# TC264MCU.net
KiCad netlist of a schematic drawn in Altium Designer
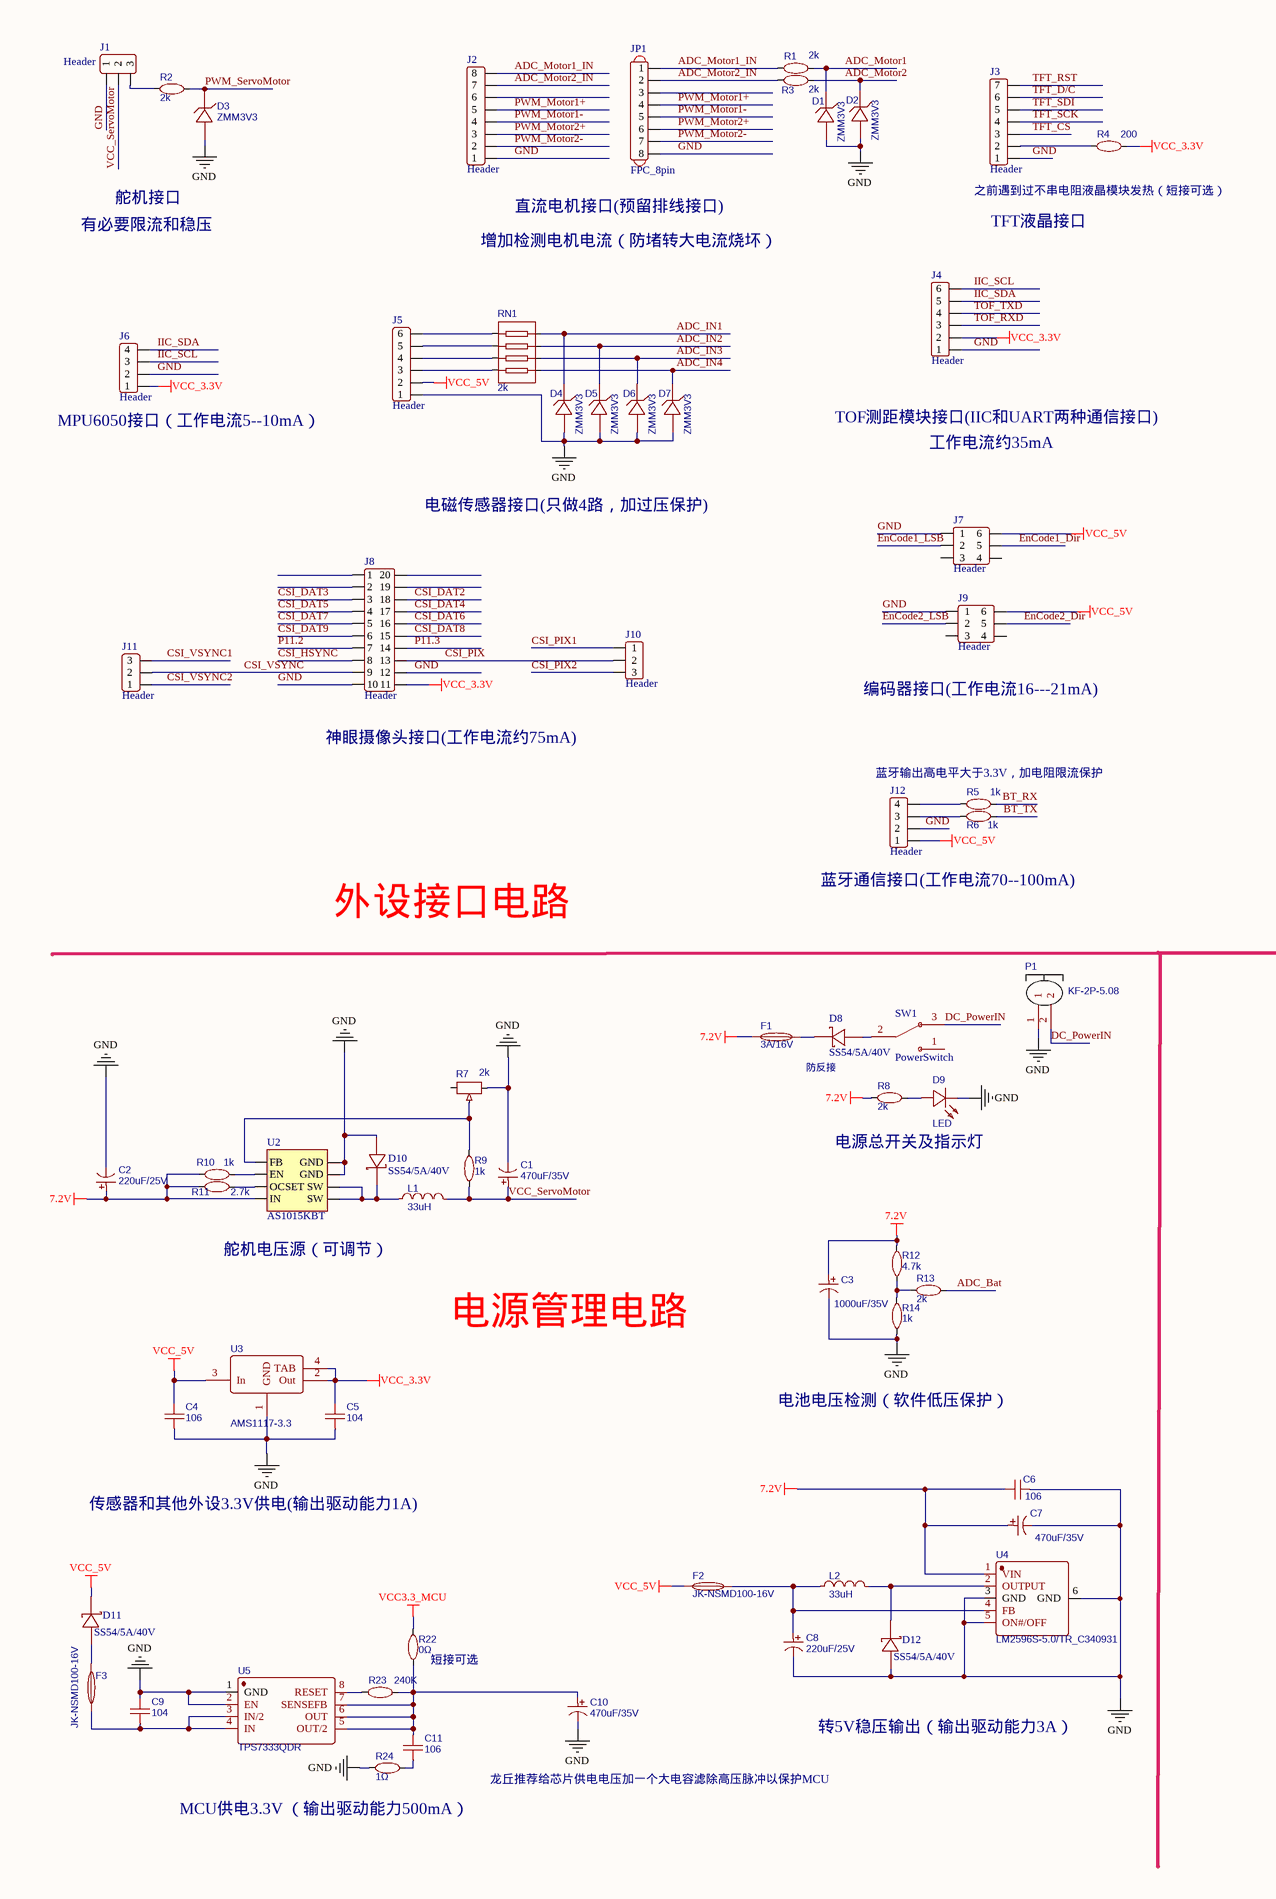
[diagram p0: TC264MCU.SchDoc, left]
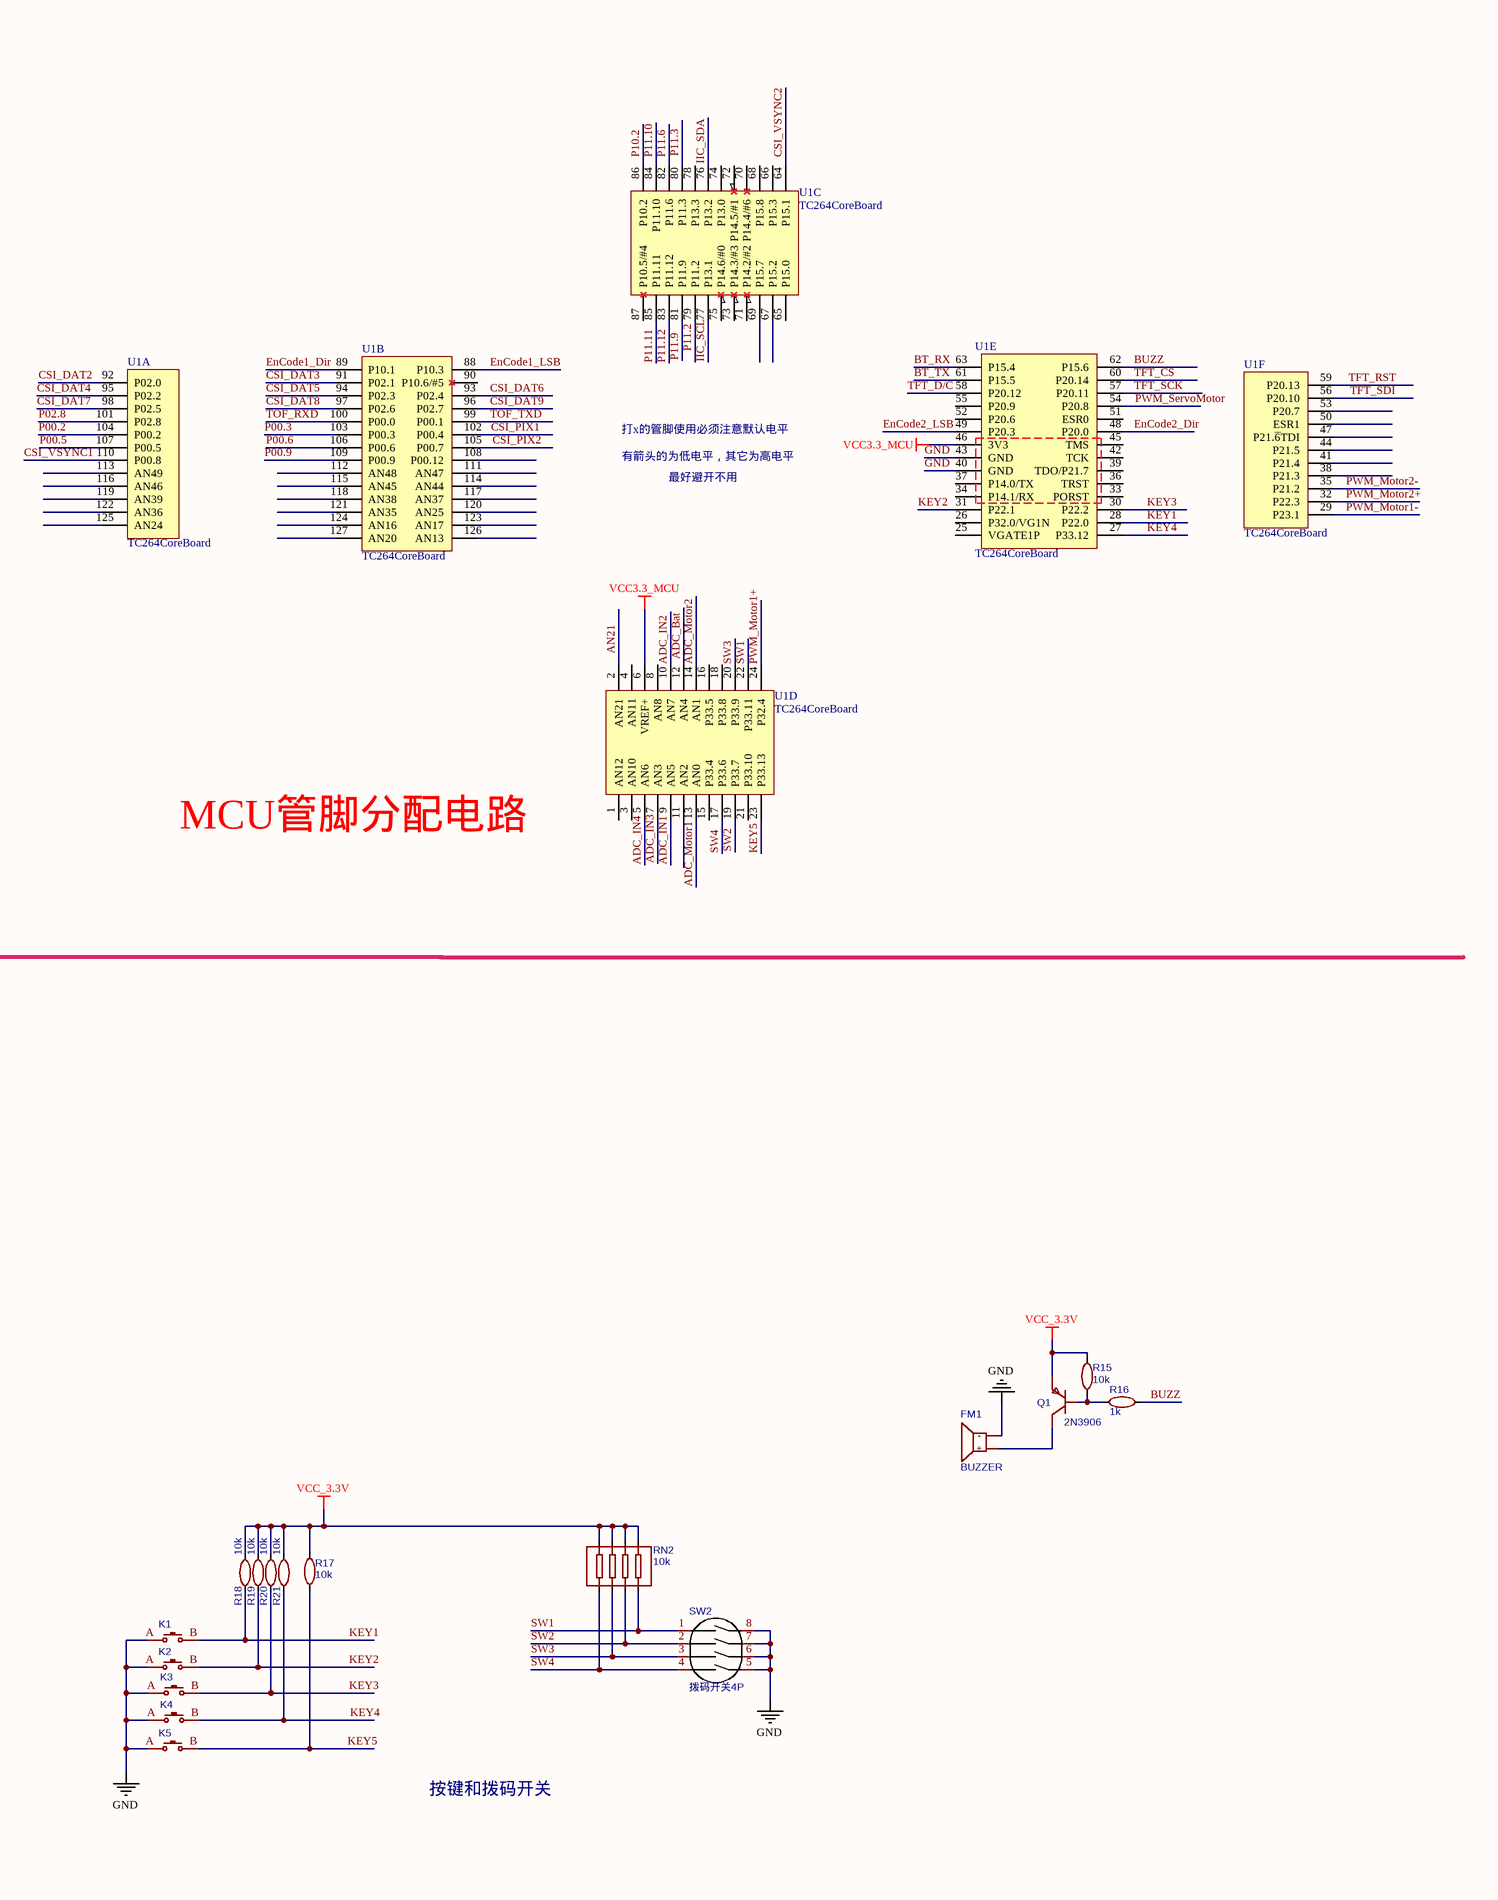
[diagram p1: TC264MCU.SchDoc, right]

(export (version "E")
  (design (tool "Eeschema 10.0.6"))
  (components
    (comp (ref "C1")
      (value "470uF/35V")
      (footprint "CAPE_SMD_F_8.4")
      (description "贴片电解电容")
      (fields
        (field (name "BOM_MANUFACTURER PART") "RVT1C221M0607")
        (field (name "BOM_SUPPLIER PART") "C72496")
      )
      (libsource (lib "LTC_Library1") (part "CAP_E_SMD"))
    )
    (comp (ref "C2")
      (value "220uF/25V")
      (footprint "CAPE_SMD_D_6.4")
      (description "贴片电解电容")
      (fields
        (field (name "BOM_MANUFACTURER PART") "RVT1C221M0607")
        (field (name "BOM_SUPPLIER PART") "C72496")
      )
      (libsource (lib "LTC_Library1") (part "CAP_E_SMD"))
    )
    (comp (ref "C3")
      (value "1000uF/35V")
      (footprint "CAPE_SMD_G_10.6")
      (description "贴片电解电容")
      (fields
        (field (name "BOM_MANUFACTURER PART") "RVT1C221M0607")
        (field (name "BOM_SUPPLIER PART") "C72496")
      )
      (libsource (lib "LTC_Library1") (part "CAP_E_SMD"))
    )
    (comp (ref "C4")
      (value "106")
      (footprint "CAP_0603")
      (fields
        (field (name "BOM_SUPPLIER PART") "C307348")
        (field (name "BOM_MANUFACTURER PART") "CL10B104KB8WPNC")
        (field (name "CONTRIBUTOR") "LCSC")
      )
      (libsource (lib "LTC_Library1") (part "CAP_0603"))
    )
    (comp (ref "C5")
      (value "104")
      (footprint "CAP_0603")
      (fields
        (field (name "BOM_SUPPLIER PART") "C307348")
        (field (name "BOM_MANUFACTURER PART") "CL10B104KB8WPNC")
        (field (name "CONTRIBUTOR") "LCSC")
      )
      (libsource (lib "LTC_Library1") (part "CAP_0603"))
    )
    (comp (ref "C6")
      (value "106")
      (footprint "CAP_0603")
      (fields
        (field (name "BOM_SUPPLIER PART") "C307348")
        (field (name "BOM_MANUFACTURER PART") "CL10B104KB8WPNC")
        (field (name "CONTRIBUTOR") "LCSC")
      )
      (libsource (lib "LTC_Library1") (part "CAP_0603"))
    )
    (comp (ref "C7")
      (value "470uF/35V")
      (footprint "CAPE_SMD_F_8.4")
      (description "贴片电解电容")
      (fields
        (field (name "BOM_MANUFACTURER PART") "RVT1C221M0607")
        (field (name "BOM_SUPPLIER PART") "C72496")
      )
      (libsource (lib "") (part "CAP_E_SMD_1"))
    )
    (comp (ref "C8")
      (value "220uF/25V")
      (footprint "CAPE_SMD_D_6.4")
      (description "贴片电解电容")
      (fields
        (field (name "BOM_MANUFACTURER PART") "RVT1C221M0607")
        (field (name "BOM_SUPPLIER PART") "C72496")
      )
      (libsource (lib "LTC_Library1") (part "CAP_E_SMD"))
    )
    (comp (ref "C9")
      (value "104")
      (footprint "CAP_0603")
      (fields
        (field (name "BOM_SUPPLIER PART") "C307348")
        (field (name "BOM_MANUFACTURER PART") "CL10B104KB8WPNC")
        (field (name "CONTRIBUTOR") "LCSC")
      )
      (libsource (lib "LTC_Library1") (part "CAP_0603"))
    )
    (comp (ref "C10")
      (value "470uF/35V")
      (footprint "CAPE_SMD_F_8.4")
      (description "贴片电解电容")
      (fields
        (field (name "BOM_MANUFACTURER PART") "RVT1C221M0607")
        (field (name "BOM_SUPPLIER PART") "C72496")
      )
      (libsource (lib "LTC_Library1") (part "CAP_E_SMD"))
    )
    (comp (ref "C11")
      (value "106")
      (footprint "CAP_0603")
      (fields
        (field (name "BOM_SUPPLIER PART") "C307348")
        (field (name "BOM_MANUFACTURER PART") "CL10B104KB8WPNC")
        (field (name "CONTRIBUTOR") "LCSC")
      )
      (libsource (lib "LTC_Library1") (part "CAP_0603"))
    )
    (comp (ref "D1")
      (value "ZMM3V3")
      (footprint "LL-34_L3.5-W1.5-RD")
      (fields (field (name "BOM_SUPPLIER PART") "C8056"))
      (libsource (lib "SmartCar_Library") (part "ZMM3V3"))
    )
    (comp (ref "D2")
      (value "ZMM3V3")
      (footprint "LL-34_L3.5-W1.5-RD")
      (fields (field (name "BOM_SUPPLIER PART") "C8056"))
      (libsource (lib "SmartCar_Library") (part "ZMM3V3"))
    )
    (comp (ref "D3")
      (value "ZMM3V3")
      (footprint "LL-34_L3.5-W1.5-RD")
      (fields (field (name "BOM_SUPPLIER PART") "C8056"))
      (libsource (lib "SmartCar_Library") (part "ZMM3V3"))
    )
    (comp (ref "D4")
      (value "ZMM3V3")
      (footprint "LL-34_L3.5-W1.5-RD")
      (fields (field (name "BOM_SUPPLIER PART") "C8056"))
      (libsource (lib "SmartCar_Library") (part "ZMM3V3"))
    )
    (comp (ref "D5")
      (value "ZMM3V3")
      (footprint "LL-34_L3.5-W1.5-RD")
      (fields (field (name "BOM_SUPPLIER PART") "C8056"))
      (libsource (lib "SmartCar_Library") (part "ZMM3V3"))
    )
    (comp (ref "D6")
      (value "ZMM3V3")
      (footprint "LL-34_L3.5-W1.5-RD")
      (fields (field (name "BOM_SUPPLIER PART") "C8056"))
      (libsource (lib "SmartCar_Library") (part "ZMM3V3"))
    )
    (comp (ref "D7")
      (value "ZMM3V3")
      (footprint "LL-34_L3.5-W1.5-RD")
      (fields (field (name "BOM_SUPPLIER PART") "C8056"))
      (libsource (lib "SmartCar_Library") (part "ZMM3V3"))
    )
    (comp (ref "D8")
      (value "SS54/5A/40V")
      (footprint "DO214_SMA")
      (libsource (lib "LTC_Library1") (part "SS54"))
    )
    (comp (ref "D9")
      (value "LED")
      (footprint "LED_0603_B")
      (description "发光LED")
      (fields
        (field (name "BOM_MANUFACTURER PART") "D-G080508G1")
        (field (name "BOM_SUPPLIER PART") "C107402")
        (field (name "CONTRIBUTOR") "LCSC")
      )
      (libsource (lib "LTC_Library1") (part "LED_0603"))
    )
    (comp (ref "D10")
      (value "SS54/5A/40V")
      (footprint "DO214_SMA")
      (libsource (lib "LTC_Library1") (part "SS54"))
    )
    (comp (ref "D11")
      (value "SS54/5A/40V")
      (footprint "DO214_SMA")
      (libsource (lib "LTC_Library1") (part "SS54"))
    )
    (comp (ref "D12")
      (value "SS54/5A/40V")
      (footprint "DO214_SMA")
      (libsource (lib "LTC_Library1") (part "SS54"))
    )
    (comp (ref "F1")
      (value "3A/16V")
      (footprint "F1206")
      (fields
        (field (name "BOM_SUPPLIER PART") "C369161")
        (field (name "BOM_MANUFACTURER PART") "JK-NSMD100-16V")
        (field (name "CONTRIBUTOR") "LCSC")
      )
      (libsource (lib "SmartCar_Library") (part "JK-NSMD100-16V"))
    )
    (comp (ref "F2")
      (value "JK-NSMD100-16V")
      (footprint "F1206")
      (fields (field (name "BOM_SUPPLIER PART") "C369161") (field (name "CONTRIBUTOR") "LCSC"))
      (libsource (lib "SmartCar_Library") (part "JK-NSMD100-16V"))
    )
    (comp (ref "F3")
      (value "JK-NSMD100-16V")
      (footprint "F1206")
      (fields (field (name "BOM_SUPPLIER PART") "C369161") (field (name "CONTRIBUTOR") "LCSC"))
      (libsource (lib "SmartCar_Library") (part "JK-NSMD100-16V"))
    )
    (comp (ref "FM1")
      (value "BUZZER")
      (footprint "BUZZ-12*7.5")
      (description "蜂鸣器")
      (fields (field (name "BOM_MANUFACTURER PART") "TMB12A12") (field (name "BOM_SUPPLIER PART") "C96079"))
      (libsource (lib "LTC_Library1") (part "BUZZER"))
    )
    (comp (ref "J1")
      (value "Header")
      (footprint "Header 2.54X3")
      (libsource (lib "LTC_Library1") (part "Header 2.54_3"))
    )
    (comp (ref "J2")
      (value "Header")
      (footprint "Header 2.54X8")
      (libsource (lib "LTC_Library1") (part "Header 2.54_8"))
    )
    (comp (ref "J3")
      (value "Header")
      (footprint "Header F 2.54X7")
      (libsource (lib "LTC_Library1") (part "Header 2.54_7"))
    )
    (comp (ref "J4")
      (value "Header")
      (footprint "Header 2.54X6")
      (libsource (lib "LTC_Library1") (part "Header 2.54_6"))
    )
    (comp (ref "J5")
      (value "Header")
      (footprint "Header 2.54X6")
      (libsource (lib "LTC_Library1") (part "Header 2.54_6"))
    )
    (comp (ref "J6")
      (value "Header")
      (footprint "Header 2.54X4")
      (libsource (lib "LTC_Library1") (part "Header 2.54_4"))
    )
    (comp (ref "J7")
      (value "Header")
      (footprint "Header 2.54_2X3")
      (libsource (lib "LTC_Library1") (part "Header 2.54_2X3"))
    )
    (comp (ref "J8")
      (value "Header")
      (footprint "Header F 2.54_2x10")
      (libsource (lib "LTC_Library1") (part "Header 2.54_2X10"))
    )
    (comp (ref "J9")
      (value "Header")
      (footprint "Header 2.54_2X3")
      (libsource (lib "LTC_Library1") (part "Header 2.54_2X3"))
    )
    (comp (ref "J10")
      (value "Header")
      (footprint "Header 2.54X3")
      (libsource (lib "LTC_Library1") (part "Header 2.54_3"))
    )
    (comp (ref "J11")
      (value "Header")
      (footprint "Header 2.54X3")
      (libsource (lib "LTC_Library1") (part "Header 2.54_3"))
    )
    (comp (ref "J12")
      (value "Header")
      (footprint "Header F 2.54X4")
      (libsource (lib "LTC_Library1") (part "Header 2.54_4"))
    )
    (comp (ref "JP1")
      (value "FPC_8pin")
      (footprint "FPC_1.0_8P")
      (libsource (lib "LTC_Library1") (part "FPC_8pin"))
    )
    (comp (ref "K1")
      (value "TS-Button_2P")
      (footprint "SW_SMD_6.1*3.7")
      (description "贴片按键 3*6*2.5")
      (fields
        (field (name "BOM_SUPPLIER PART") "C455236")
        (field (name "BOM_MANUFACTURER PART") "TS-1007S-26")
        (field (name "CONTRIBUTOR") "LCSC")
      )
      (libsource (lib "LTC_Library1") (part "TS-Button_2P"))
    )
    (comp (ref "K2")
      (value "TS-Button_2P")
      (footprint "SW_SMD_6.1*3.7")
      (description "贴片按键 3*6*2.5")
      (fields
        (field (name "BOM_SUPPLIER PART") "C455236")
        (field (name "BOM_MANUFACTURER PART") "TS-1007S-26")
        (field (name "CONTRIBUTOR") "LCSC")
      )
      (libsource (lib "LTC_Library1") (part "TS-Button_2P"))
    )
    (comp (ref "K3")
      (value "TS-Button_2P")
      (footprint "SW_SMD_6.1*3.7")
      (description "贴片按键 3*6*2.5")
      (fields
        (field (name "BOM_SUPPLIER PART") "C455236")
        (field (name "BOM_MANUFACTURER PART") "TS-1007S-26")
        (field (name "CONTRIBUTOR") "LCSC")
      )
      (libsource (lib "LTC_Library1") (part "TS-Button_2P"))
    )
    (comp (ref "K4")
      (value "TS-Button_2P")
      (footprint "SW_SMD_6.1*3.7")
      (description "贴片按键 3*6*2.5")
      (fields
        (field (name "BOM_SUPPLIER PART") "C455236")
        (field (name "BOM_MANUFACTURER PART") "TS-1007S-26")
        (field (name "CONTRIBUTOR") "LCSC")
      )
      (libsource (lib "LTC_Library1") (part "TS-Button_2P"))
    )
    (comp (ref "K5")
      (value "TS-Button_2P")
      (footprint "SW_SMD_6.1*3.7")
      (description "贴片按键 3*6*2.5")
      (fields
        (field (name "BOM_SUPPLIER PART") "C455236")
        (field (name "BOM_MANUFACTURER PART") "TS-1007S-26")
        (field (name "CONTRIBUTOR") "LCSC")
      )
      (libsource (lib "LTC_Library1") (part "TS-Button_2P"))
    )
    (comp (ref "L1")
      (value "33uH")
      (footprint "IND-SMD_L8.0-W8.0")
      (fields
        (field (name "BOM_SUPPLIER PART") "C295130")
        (field (name "BOM_MANUFACTURER PART") "NLV25T-330J-EF")
        (field (name "CONTRIBUTOR") "LCSC")
      )
      (libsource (lib "SmartCar_Library") (part "Inductor"))
    )
    (comp (ref "L2")
      (value "33uH")
      (footprint "IND-SMD_L8.0-W8.0")
      (fields
        (field (name "BOM_SUPPLIER PART") "C295130")
        (field (name "BOM_MANUFACTURER PART") "NLV25T-330J-EF")
        (field (name "CONTRIBUTOR") "LCSC")
      )
      (libsource (lib "SmartCar_Library") (part "Inductor"))
    )
    (comp (ref "P1")
      (value "KF-2P-5.08")
      (footprint "KF_2P-5.08")
      (description "端子2P")
      (fields
        (field (name "BOM_MANUFACTURER PART") "WJ500H-5.08-2P")
        (field (name "BOM_SUPPLIER PART") "C8478")
      )
      (libsource (lib "LTC_Library1") (part "KF-2P-5.08"))
    )
    (comp (ref "Q1")
      (value "2N3906")
      (footprint "TO_92A")
      (description "三极管PNP")
      (fields (field (name "BOM_SUPPLIER PART") "C305396") (field (name "CONTRIBUTOR") "LCSC"))
      (libsource (lib "LTC_Library1") (part "2N3906"))
    )
    (comp (ref "R1")
      (value "2k")
      (footprint "RES_0603")
      (fields
        (field (name "BOM_MANUFACTURER PART") "RC0402JR-07100KL")
        (field (name "BOM_SUPPLIER PART") "C106234")
      )
      (libsource (lib "LTC_Library1") (part "RES_0603"))
    )
    (comp (ref "R2")
      (value "2k")
      (footprint "RES_0603")
      (fields
        (field (name "BOM_MANUFACTURER PART") "RC0402JR-07100KL")
        (field (name "BOM_SUPPLIER PART") "C106234")
      )
      (libsource (lib "LTC_Library1") (part "RES_0603"))
    )
    (comp (ref "R3")
      (value "2k")
      (footprint "RES_0603")
      (fields
        (field (name "BOM_MANUFACTURER PART") "RC0402JR-07100KL")
        (field (name "BOM_SUPPLIER PART") "C106234")
      )
      (libsource (lib "LTC_Library1") (part "RES_0603"))
    )
    (comp (ref "R4")
      (value "200")
      (footprint "RES_0603")
      (fields
        (field (name "BOM_MANUFACTURER PART") "RC0402JR-07100KL")
        (field (name "BOM_SUPPLIER PART") "C106234")
      )
      (libsource (lib "LTC_Library1") (part "RES_0603"))
    )
    (comp (ref "R5")
      (value "1k")
      (footprint "RES_0603")
      (fields
        (field (name "BOM_MANUFACTURER PART") "RC0402JR-07100KL")
        (field (name "BOM_SUPPLIER PART") "C106234")
      )
      (libsource (lib "LTC_Library1") (part "RES_0603"))
    )
    (comp (ref "R6")
      (value "1k")
      (footprint "RES_0603")
      (fields
        (field (name "BOM_MANUFACTURER PART") "RC0402JR-07100KL")
        (field (name "BOM_SUPPLIER PART") "C106234")
      )
      (libsource (lib "LTC_Library1") (part "RES_0603"))
    )
    (comp (ref "R7")
      (value "2k")
      (footprint "RES_POT-3296W")
      (description "可调电阻3296W")
      (fields
        (field (name "BOM_SUPPLIER PART") "C118963")
        (field (name "BOM_MANUFACTURER PART") "3296W-1-104")
        (field (name "CONTRIBUTOR") "LCSC")
      )
      (libsource (lib "LTC_Library1") (part "RES_POT-3296W"))
    )
    (comp (ref "R8")
      (value "2k")
      (footprint "RES_0603")
      (fields
        (field (name "BOM_MANUFACTURER PART") "RC0402JR-07100KL")
        (field (name "BOM_SUPPLIER PART") "C106234")
      )
      (libsource (lib "LTC_Library1") (part "RES_0603"))
    )
    (comp (ref "R9")
      (value "1k")
      (footprint "RES_0603")
      (fields
        (field (name "BOM_MANUFACTURER PART") "RC0402JR-07100KL")
        (field (name "BOM_SUPPLIER PART") "C106234")
      )
      (libsource (lib "LTC_Library1") (part "RES_0603"))
    )
    (comp (ref "R10")
      (value "1k")
      (footprint "RES_0603")
      (fields
        (field (name "BOM_MANUFACTURER PART") "RC0402JR-07100KL")
        (field (name "BOM_SUPPLIER PART") "C106234")
      )
      (libsource (lib "LTC_Library1") (part "RES_0603"))
    )
    (comp (ref "R11")
      (value "2.7k")
      (footprint "RES_0603")
      (fields
        (field (name "BOM_MANUFACTURER PART") "RC0402JR-07100KL")
        (field (name "BOM_SUPPLIER PART") "C106234")
      )
      (libsource (lib "LTC_Library1") (part "RES_0603"))
    )
    (comp (ref "R12")
      (value "4.7k")
      (footprint "RES_0603")
      (fields
        (field (name "BOM_MANUFACTURER PART") "RC0402JR-07100KL")
        (field (name "BOM_SUPPLIER PART") "C106234")
      )
      (libsource (lib "LTC_Library1") (part "RES_0603"))
    )
    (comp (ref "R13")
      (value "2k")
      (footprint "RES_0603")
      (fields
        (field (name "BOM_MANUFACTURER PART") "RC0402JR-07100KL")
        (field (name "BOM_SUPPLIER PART") "C106234")
      )
      (libsource (lib "LTC_Library1") (part "RES_0603"))
    )
    (comp (ref "R14")
      (value "1k")
      (footprint "RES_0603")
      (fields
        (field (name "BOM_MANUFACTURER PART") "RC0402JR-07100KL")
        (field (name "BOM_SUPPLIER PART") "C106234")
      )
      (libsource (lib "LTC_Library1") (part "RES_0603"))
    )
    (comp (ref "R15")
      (value "10k")
      (footprint "RES_0603")
      (fields
        (field (name "BOM_MANUFACTURER PART") "RC0402JR-07100KL")
        (field (name "BOM_SUPPLIER PART") "C106234")
      )
      (libsource (lib "LTC_Library1") (part "RES_0603"))
    )
    (comp (ref "R16")
      (value "1k")
      (footprint "RES_0603")
      (fields
        (field (name "BOM_MANUFACTURER PART") "RC0402JR-07100KL")
        (field (name "BOM_SUPPLIER PART") "C106234")
      )
      (libsource (lib "LTC_Library1") (part "RES_0603"))
    )
    (comp (ref "R17")
      (value "10k")
      (footprint "RES_0603")
      (fields
        (field (name "BOM_MANUFACTURER PART") "RC0402JR-07100KL")
        (field (name "BOM_SUPPLIER PART") "C106234")
      )
      (libsource (lib "LTC_Library1") (part "RES_0603"))
    )
    (comp (ref "R18")
      (value "10k")
      (footprint "RES_0603")
      (fields
        (field (name "BOM_MANUFACTURER PART") "RC0402JR-07100KL")
        (field (name "BOM_SUPPLIER PART") "C106234")
      )
      (libsource (lib "LTC_Library1") (part "RES_0603"))
    )
    (comp (ref "R19")
      (value "10k")
      (footprint "RES_0603")
      (fields
        (field (name "BOM_MANUFACTURER PART") "RC0402JR-07100KL")
        (field (name "BOM_SUPPLIER PART") "C106234")
      )
      (libsource (lib "LTC_Library1") (part "RES_0603"))
    )
    (comp (ref "R20")
      (value "10k")
      (footprint "RES_0603")
      (fields
        (field (name "BOM_MANUFACTURER PART") "RC0402JR-07100KL")
        (field (name "BOM_SUPPLIER PART") "C106234")
      )
      (libsource (lib "LTC_Library1") (part "RES_0603"))
    )
    (comp (ref "R21")
      (value "10k")
      (footprint "RES_0603")
      (fields
        (field (name "BOM_MANUFACTURER PART") "RC0402JR-07100KL")
        (field (name "BOM_SUPPLIER PART") "C106234")
      )
      (libsource (lib "LTC_Library1") (part "RES_0603"))
    )
    (comp (ref "R22")
      (value "0Ω")
      (footprint "RES_0603")
      (fields
        (field (name "BOM_MANUFACTURER PART") "RC0402JR-07100KL")
        (field (name "BOM_SUPPLIER PART") "C106234")
      )
      (libsource (lib "LTC_Library1") (part "RES_0603"))
    )
    (comp (ref "R23")
      (value "240K")
      (footprint "RES_0603")
      (fields
        (field (name "BOM_MANUFACTURER PART") "RC0402JR-07100KL")
        (field (name "BOM_SUPPLIER PART") "C106234")
      )
      (libsource (lib "LTC_Library1") (part "RES_0603"))
    )
    (comp (ref "R24")
      (value "1Ω")
      (footprint "RES_0603")
      (fields
        (field (name "BOM_MANUFACTURER PART") "RC0402JR-07100KL")
        (field (name "BOM_SUPPLIER PART") "C106234")
      )
      (libsource (lib "LTC_Library1") (part "RES_0603"))
    )
    (comp (ref "RN1")
      (value "2k")
      (footprint "RES-ARRAY-SMD_0603-8P-L3.2-W1.6-BL")
      (fields
        (field (name "BOM_MANUFACTURER PART") "YC164-JR-0710KL")
        (field (name "BOM_SUPPLIER PART") "C107374")
      )
      (libsource (lib "SmartCar_Library") (part "RESW4"))
    )
    (comp (ref "RN2")
      (value "10k")
      (footprint "RES-ARRAY-SMD_0603-8P-L3.2-W1.6-BL")
      (fields
        (field (name "BOM_MANUFACTURER PART") "YC164-JR-0710KL")
        (field (name "BOM_SUPPLIER PART") "C107374")
      )
      (libsource (lib "SmartCar_Library") (part "RESW4"))
    )
    (comp (ref "SW1")
      (value "PowerSwitch")
      (footprint "SW-TH_K3-1260D-K1")
      (libsource (lib "SmartCar_Library") (part "PowerSwitch"))
    )
    (comp (ref "SW2")
      (value "拨码开关4P")
      (footprint "MCEMR-04-T")
      (description "DIP_4PX2*2.54")
      (fields
        (field (name "BOM_MANUFACTURER PART") "VDG/S-04HG-R")
        (field (name "BOM_SUPPLIER PART") "C15781")
      )
      (libsource (lib "LTC_Library1") (part "拨码开关4P"))
    )
    (comp (ref "U1")
      (value "TC264CoreBoard")
      (footprint "LQ-TC264-SYSVC-S")
      (libsource (lib "SmartCar_Library") (part "TC264CoreBoard"))
    )
    (comp (ref "U2")
      (value "AS1015KBT")
      (footprint "SOIC-8_150MIL")
      (libsource (lib "SmartCar_Library") (part "AS1015KBT"))
    )
    (comp (ref "U3")
      (value "AMS1117-3.3")
      (footprint "SOT-223_3")
      (fields (field (name "BOM_SUPPLIER PART") "C165482") (field (name "CONTRIBUTOR") "LCSC"))
      (libsource (lib "LTC_Library1") (part "AMS1117-3.3"))
    )
    (comp (ref "U4")
      (value "LM2596S-5.0/TR_C340931")
      (footprint "TO-263_5")
      (fields
        (field (name "BOM_SUPPLIER PART") "C340931")
        (field (name "BOM_MANUFACTURER PART") "LM2596S-5.0/TR")
        (field (name "CONTRIBUTOR") "LCSC")
      )
      (libsource (lib "LTC_Library1") (part "LM2596S-5.0/TR_C340931"))
    )
    (comp (ref "U5")
      (value "TPS7333QDR")
      (footprint "SOIC-8_150MIL")
      (fields (field (name "BOM_SUPPLIER PART") "C23791"))
      (libsource (lib "LTC_Library1") (part "TPS7333QDR"))
    )
  )
  (nets
    (net (code "1") (name "/ADC_Bat") (class "Default")
      (node (ref "R13") (pin "2") (pinfunction "2_2") (pintype "passive"))
      (node (ref "U1") (pin "12") (pinfunction "AN4_12") (pintype "passive"))
    )
    (net (code "2") (name "/ADC_IN1") (class "Default")
      (node (ref "D4") (pin "1") (pinfunction "C_1") (pintype "passive"))
      (node (ref "RN1") (pin "8") (pinfunction "8_8") (pintype "passive"))
      (node (ref "U1") (pin "9") (pinfunction "AN5_9") (pintype "passive"))
    )
    (net (code "3") (name "/ADC_IN2") (class "Default")
      (node (ref "D5") (pin "1") (pinfunction "C_1") (pintype "passive"))
      (node (ref "RN1") (pin "7") (pinfunction "7_7") (pintype "passive"))
      (node (ref "U1") (pin "10") (pinfunction "AN7_10") (pintype "passive"))
    )
    (net (code "4") (name "/ADC_IN3") (class "Default")
      (node (ref "D6") (pin "1") (pinfunction "C_1") (pintype "passive"))
      (node (ref "RN1") (pin "6") (pinfunction "6_6") (pintype "passive"))
      (node (ref "U1") (pin "7") (pinfunction "AN3_7") (pintype "passive"))
    )
    (net (code "5") (name "/ADC_IN4") (class "Default")
      (node (ref "D7") (pin "1") (pinfunction "C_1") (pintype "passive"))
      (node (ref "RN1") (pin "5") (pinfunction "5_5") (pintype "passive"))
      (node (ref "U1") (pin "5") (pinfunction "AN6_5") (pintype "passive"))
    )
    (net (code "6") (name "/ADC_Motor1") (class "Default")
      (node (ref "D1") (pin "1") (pinfunction "C_1") (pintype "passive"))
      (node (ref "R1") (pin "1") (pinfunction "1_1") (pintype "passive"))
      (node (ref "U1") (pin "13") (pinfunction "AN0_13") (pintype "passive"))
    )
    (net (code "7") (name "/ADC_Motor1_IN") (class "Default")
      (node (ref "J2") (pin "8") (pinfunction "8_8") (pintype "passive"))
      (node (ref "JP1") (pin "1") (pinfunction "1_1") (pintype "passive"))
      (node (ref "R1") (pin "2") (pinfunction "2_2") (pintype "passive"))
    )
    (net (code "8") (name "/ADC_Motor2") (class "Default")
      (node (ref "D2") (pin "1") (pinfunction "C_1") (pintype "passive"))
      (node (ref "R3") (pin "1") (pinfunction "1_1") (pintype "passive"))
      (node (ref "U1") (pin "14") (pinfunction "AN1_14") (pintype "passive"))
    )
    (net (code "9") (name "/ADC_Motor2_IN") (class "Default")
      (node (ref "J2") (pin "7") (pinfunction "7_7") (pintype "passive"))
      (node (ref "JP1") (pin "2") (pinfunction "2_2") (pintype "passive"))
      (node (ref "R3") (pin "2") (pinfunction "2_2") (pintype "passive"))
    )
    (net (code "10") (name "/AN21") (class "Default")
      (node (ref "U1") (pin "2") (pinfunction "AN21_2") (pintype "passive"))
    )
    (net (code "11") (name "/BT_RX") (class "Default")
      (node (ref "R5") (pin "1") (pinfunction "1_1") (pintype "passive"))
      (node (ref "U1") (pin "63") (pinfunction "P15.4_63") (pintype "passive"))
    )
    (net (code "12") (name "/BT_TX") (class "Default")
      (node (ref "R6") (pin "1") (pinfunction "1_1") (pintype "passive"))
      (node (ref "U1") (pin "61") (pinfunction "P15.5_61") (pintype "passive"))
    )
    (net (code "13") (name "/BUZZ") (class "Default")
      (node (ref "R16") (pin "1") (pinfunction "1_1") (pintype "passive"))
      (node (ref "U1") (pin "62") (pinfunction "P15.6_62") (pintype "passive"))
    )
    (net (code "14") (name "/CSI_DAT2") (class "Default")
      (node (ref "J8") (pin "18") (pinfunction "18_18") (pintype "passive"))
      (node (ref "U1") (pin "92") (pinfunction "P02.0_92") (pintype "passive"))
    )
    (net (code "15") (name "/CSI_DAT3") (class "Default")
      (node (ref "J8") (pin "3") (pinfunction "3_3") (pintype "passive"))
      (node (ref "U1") (pin "91") (pinfunction "P02.1_91") (pintype "passive"))
    )
    (net (code "16") (name "/CSI_DAT4") (class "Default")
      (node (ref "J8") (pin "17") (pinfunction "17_17") (pintype "passive"))
      (node (ref "U1") (pin "95") (pinfunction "P02.2_95") (pintype "passive"))
    )
    (net (code "17") (name "/CSI_DAT5") (class "Default")
      (node (ref "J8") (pin "4") (pinfunction "4_4") (pintype "passive"))
      (node (ref "U1") (pin "94") (pinfunction "P02.3_94") (pintype "passive"))
    )
    (net (code "18") (name "/CSI_DAT6") (class "Default")
      (node (ref "J8") (pin "16") (pinfunction "16_16") (pintype "passive"))
      (node (ref "U1") (pin "93") (pinfunction "P02.4_93") (pintype "passive"))
    )
    (net (code "19") (name "/CSI_DAT7") (class "Default")
      (node (ref "J8") (pin "5") (pinfunction "5_5") (pintype "passive"))
      (node (ref "U1") (pin "98") (pinfunction "P02.5_98") (pintype "passive"))
    )
    (net (code "20") (name "/CSI_DAT8") (class "Default")
      (node (ref "J8") (pin "15") (pinfunction "15_15") (pintype "passive"))
      (node (ref "U1") (pin "97") (pinfunction "P02.6_97") (pintype "passive"))
    )
    (net (code "21") (name "/CSI_DAT9") (class "Default")
      (node (ref "J8") (pin "6") (pinfunction "6_6") (pintype "passive"))
      (node (ref "U1") (pin "96") (pinfunction "P02.7_96") (pintype "passive"))
    )
    (net (code "22") (name "/CSI_HSYNC") (class "Default")
      (node (ref "J8") (pin "8") (pinfunction "8_8") (pintype "passive"))
    )
    (net (code "23") (name "/CSI_PIX") (class "Default")
      (node (ref "J10") (pin "2") (pinfunction "2_2") (pintype "passive"))
      (node (ref "J8") (pin "13") (pinfunction "13_13") (pintype "passive"))
    )
    (net (code "24") (name "/CSI_PIX1") (class "Default")
      (node (ref "J10") (pin "1") (pinfunction "1_1") (pintype "passive"))
      (node (ref "U1") (pin "102") (pinfunction "P00.4_102") (pintype "passive"))
    )
    (net (code "25") (name "/CSI_PIX2") (class "Default")
      (node (ref "J10") (pin "3") (pinfunction "3_3") (pintype "passive"))
      (node (ref "U1") (pin "105") (pinfunction "P00.7_105") (pintype "passive"))
    )
    (net (code "26") (name "/CSI_VSYNC") (class "Default")
      (node (ref "J11") (pin "2") (pinfunction "2_2") (pintype "passive"))
      (node (ref "J8") (pin "9") (pinfunction "9_9") (pintype "passive"))
    )
    (net (code "27") (name "/CSI_VSYNC1") (class "Default")
      (node (ref "J11") (pin "3") (pinfunction "3_3") (pintype "passive"))
      (node (ref "U1") (pin "110") (pinfunction "P00.8_110") (pintype "passive"))
    )
    (net (code "28") (name "/CSI_VSYNC2") (class "Default")
      (node (ref "J11") (pin "1") (pinfunction "1_1") (pintype "passive"))
      (node (ref "U1") (pin "64") (pinfunction "P15.1_64") (pintype "passive"))
    )
    (net (code "29") (name "/DC_PowerIN") (class "Default")
      (node (ref "P1") (pin "2") (pinfunction "2_2") (pintype "passive"))
      (node (ref "SW1") (pin "3") (pinfunction "NC_3") (pintype "passive"))
    )
    (net (code "30") (name "/EnCode1_Dir") (class "Default")
      (node (ref "J7") (pin "5") (pinfunction "5_5") (pintype "passive"))
      (node (ref "U1") (pin "89") (pinfunction "P10.1_89") (pintype "passive"))
    )
    (net (code "31") (name "/EnCode1_LSB") (class "Default")
      (node (ref "J7") (pin "2") (pinfunction "2_2") (pintype "passive"))
      (node (ref "U1") (pin "88") (pinfunction "P10.3_88") (pintype "passive"))
    )
    (net (code "32") (name "/EnCode2_Dir") (class "Default")
      (node (ref "J9") (pin "5") (pinfunction "5_5") (pintype "passive"))
      (node (ref "U1") (pin "48") (pinfunction "P20.0_48") (pintype "passive"))
    )
    (net (code "33") (name "/EnCode2_LSB") (class "Default")
      (node (ref "J9") (pin "2") (pinfunction "2_2") (pintype "passive"))
      (node (ref "U1") (pin "49") (pinfunction "P20.3_49") (pintype "passive"))
    )
    (net (code "34") (name "/IIC_SCL") (class "Default")
      (node (ref "J4") (pin "6") (pinfunction "6_6") (pintype "passive"))
      (node (ref "J6") (pin "3") (pinfunction "3_3") (pintype "passive"))
      (node (ref "U1") (pin "77") (pinfunction "P13.1_77") (pintype "passive"))
    )
    (net (code "35") (name "/IIC_SDA") (class "Default")
      (node (ref "J4") (pin "5") (pinfunction "5_5") (pintype "passive"))
      (node (ref "J6") (pin "4") (pinfunction "4_4") (pintype "passive"))
      (node (ref "U1") (pin "76") (pinfunction "P13.2_76") (pintype "passive"))
    )
    (net (code "36") (name "/KEY1") (class "Default")
      (node (ref "K1") (pin "B") (pinfunction "B_B") (pintype "passive"))
      (node (ref "R18") (pin "1") (pinfunction "1_1") (pintype "passive"))
      (node (ref "U1") (pin "28") (pinfunction "P22.0_28") (pintype "passive"))
    )
    (net (code "37") (name "/KEY2") (class "Default")
      (node (ref "K2") (pin "B") (pinfunction "B_B") (pintype "passive"))
      (node (ref "R19") (pin "1") (pinfunction "1_1") (pintype "passive"))
      (node (ref "U1") (pin "31") (pinfunction "P22.1_31") (pintype "passive"))
    )
    (net (code "38") (name "/KEY3") (class "Default")
      (node (ref "K3") (pin "B") (pinfunction "B_B") (pintype "passive"))
      (node (ref "R20") (pin "1") (pinfunction "1_1") (pintype "passive"))
      (node (ref "U1") (pin "30") (pinfunction "P22.2_30") (pintype "passive"))
    )
    (net (code "39") (name "/KEY4") (class "Default")
      (node (ref "K4") (pin "B") (pinfunction "B_B") (pintype "passive"))
      (node (ref "R21") (pin "1") (pinfunction "1_1") (pintype "passive"))
      (node (ref "U1") (pin "27") (pinfunction "P33.12_27") (pintype "passive"))
    )
    (net (code "40") (name "/KEY5") (class "Default")
      (node (ref "K5") (pin "B") (pinfunction "B_B") (pintype "passive"))
      (node (ref "R17") (pin "1") (pinfunction "1_1") (pintype "passive"))
      (node (ref "U1") (pin "23") (pinfunction "P33.13_23") (pintype "passive"))
    )
    (net (code "41") (name "/P00.2") (class "Default")
      (node (ref "U1") (pin "104") (pinfunction "P00.2_104") (pintype "passive"))
    )
    (net (code "42") (name "/P00.3") (class "Default")
      (node (ref "U1") (pin "103") (pinfunction "P00.3_103") (pintype "passive"))
    )
    (net (code "43") (name "/P00.5") (class "Default")
      (node (ref "U1") (pin "107") (pinfunction "P00.5_107") (pintype "passive"))
    )
    (net (code "44") (name "/P00.6") (class "Default")
      (node (ref "U1") (pin "106") (pinfunction "P00.6_106") (pintype "passive"))
    )
    (net (code "45") (name "/P00.9") (class "Default")
      (node (ref "U1") (pin "109") (pinfunction "P00.9_109") (pintype "passive"))
    )
    (net (code "46") (name "/P02.8") (class "Default")
      (node (ref "U1") (pin "101") (pinfunction "P02.8_101") (pintype "passive"))
    )
    (net (code "47") (name "/P10.2") (class "Default")
      (node (ref "U1") (pin "86") (pinfunction "P10.2_86") (pintype "passive"))
    )
    (net (code "48") (name "/P11.2") (class "Default")
      (node (ref "J8") (pin "7") (pinfunction "7_7") (pintype "passive"))
      (node (ref "U1") (pin "79") (pinfunction "P11.2_79") (pintype "passive"))
    )
    (net (code "49") (name "/P11.3") (class "Default")
      (node (ref "J8") (pin "14") (pinfunction "14_14") (pintype "passive"))
      (node (ref "U1") (pin "80") (pinfunction "P11.3_80") (pintype "passive"))
    )
    (net (code "50") (name "/P11.6") (class "Default")
      (node (ref "U1") (pin "82") (pinfunction "P11.6_82") (pintype "passive"))
    )
    (net (code "51") (name "/P11.9") (class "Default")
      (node (ref "U1") (pin "81") (pinfunction "P11.9_81") (pintype "passive"))
    )
    (net (code "52") (name "/P11.10") (class "Default")
      (node (ref "U1") (pin "84") (pinfunction "P11.10_84") (pintype "passive"))
    )
    (net (code "53") (name "/P11.11") (class "Default")
      (node (ref "U1") (pin "85") (pinfunction "P11.11_85") (pintype "passive"))
    )
    (net (code "54") (name "/P11.12") (class "Default")
      (node (ref "U1") (pin "83") (pinfunction "P11.12_83") (pintype "passive"))
    )
    (net (code "55") (name "/PWM_Motor1+") (class "Default")
      (node (ref "J2") (pin "5") (pinfunction "5_5") (pintype "passive"))
      (node (ref "JP1") (pin "4") (pinfunction "4_4") (pintype "passive"))
      (node (ref "U1") (pin "24") (pinfunction "P32.4_24") (pintype "passive"))
    )
    (net (code "56") (name "/PWM_Motor1-") (class "Default")
      (node (ref "J2") (pin "4") (pinfunction "4_4") (pintype "passive"))
      (node (ref "JP1") (pin "5") (pinfunction "5_5") (pintype "passive"))
      (node (ref "U1") (pin "29") (pinfunction "P23.1_29") (pintype "passive"))
    )
    (net (code "57") (name "/PWM_Motor2+") (class "Default")
      (node (ref "J2") (pin "3") (pinfunction "3_3") (pintype "passive"))
      (node (ref "JP1") (pin "6") (pinfunction "6_6") (pintype "passive"))
      (node (ref "U1") (pin "32") (pinfunction "P22.3_32") (pintype "passive"))
    )
    (net (code "58") (name "/PWM_Motor2-") (class "Default")
      (node (ref "J2") (pin "2") (pinfunction "2_2") (pintype "passive"))
      (node (ref "JP1") (pin "7") (pinfunction "7_7") (pintype "passive"))
      (node (ref "U1") (pin "35") (pinfunction "P21.2_35") (pintype "passive"))
    )
    (net (code "59") (name "/PWM_ServoMotor") (class "Default")
      (node (ref "D3") (pin "1") (pinfunction "C_1") (pintype "passive"))
      (node (ref "R2") (pin "1") (pinfunction "1_1") (pintype "passive"))
      (node (ref "U1") (pin "54") (pinfunction "P20.8_54") (pintype "passive"))
    )
    (net (code "60") (name "/SW1") (class "Default")
      (node (ref "RN2") (pin "4") (pinfunction "4_4") (pintype "passive"))
      (node (ref "SW2") (pin "1") (pinfunction "1_1") (pintype "passive"))
      (node (ref "U1") (pin "22") (pinfunction "P33.11_22") (pintype "passive"))
    )
    (net (code "61") (name "/SW2") (class "Default")
      (node (ref "RN2") (pin "3") (pinfunction "3_3") (pintype "passive"))
      (node (ref "SW2") (pin "2") (pinfunction "2_2") (pintype "passive"))
      (node (ref "U1") (pin "19") (pinfunction "P33.7_19") (pintype "passive"))
    )
    (net (code "62") (name "/SW3") (class "Default")
      (node (ref "RN2") (pin "2") (pinfunction "2_2") (pintype "passive"))
      (node (ref "SW2") (pin "3") (pinfunction "3_3") (pintype "passive"))
      (node (ref "U1") (pin "20") (pinfunction "P33.9_20") (pintype "passive"))
    )
    (net (code "63") (name "/SW4") (class "Default")
      (node (ref "RN2") (pin "1") (pinfunction "1_1") (pintype "passive"))
      (node (ref "SW2") (pin "4") (pinfunction "4_4") (pintype "passive"))
      (node (ref "U1") (pin "17") (pinfunction "P33.6_17") (pintype "passive"))
    )
    (net (code "64") (name "/TFT_CS") (class "Default")
      (node (ref "J3") (pin "3") (pinfunction "3_3") (pintype "passive"))
      (node (ref "U1") (pin "60") (pinfunction "P20.14_60") (pintype "passive"))
    )
    (net (code "65") (name "/TFT_D{slash}C") (class "Default")
      (node (ref "J3") (pin "6") (pinfunction "6_6") (pintype "passive"))
      (node (ref "U1") (pin "58") (pinfunction "P20.12_58") (pintype "passive"))
    )
    (net (code "66") (name "/TFT_RST") (class "Default")
      (node (ref "J3") (pin "7") (pinfunction "7_7") (pintype "passive"))
      (node (ref "U1") (pin "59") (pinfunction "P20.13_59") (pintype "passive"))
    )
    (net (code "67") (name "/TFT_SCK") (class "Default")
      (node (ref "J3") (pin "4") (pinfunction "4_4") (pintype "passive"))
      (node (ref "U1") (pin "57") (pinfunction "P20.11_57") (pintype "passive"))
    )
    (net (code "68") (name "/TFT_SDI") (class "Default")
      (node (ref "J3") (pin "5") (pinfunction "5_5") (pintype "passive"))
      (node (ref "U1") (pin "56") (pinfunction "P20.10_56") (pintype "passive"))
    )
    (net (code "69") (name "/TOF_RXD") (class "Default")
      (node (ref "J4") (pin "3") (pinfunction "3_3") (pintype "passive"))
      (node (ref "U1") (pin "100") (pinfunction "P00.0_100") (pintype "passive"))
    )
    (net (code "70") (name "/TOF_TXD") (class "Default")
      (node (ref "J4") (pin "4") (pinfunction "4_4") (pintype "passive"))
      (node (ref "U1") (pin "99") (pinfunction "P00.1_99") (pintype "passive"))
    )
    (net (code "71") (name "/VCC_ServoMotor") (class "Default")
      (node (ref "C1") (pin "1") (pinfunction "1_1") (pintype "passive"))
      (node (ref "J1") (pin "2") (pinfunction "2_2") (pintype "passive"))
      (node (ref "L1") (pin "2") (pinfunction "2_2") (pintype "passive"))
      (node (ref "R9") (pin "1") (pinfunction "1_1") (pintype "passive"))
    )
    (net (code "72") (name "7.2V") (class "Default")
      (node (ref "C2") (pin "1") (pinfunction "1_1") (pintype "passive"))
      (node (ref "C3") (pin "1") (pinfunction "1_1") (pintype "passive"))
      (node (ref "C6") (pin "1") (pinfunction "1_1") (pintype "passive"))
      (node (ref "C7") (pin "1") (pinfunction "1_1") (pintype "passive"))
      (node (ref "F1") (pin "2") (pinfunction "2_2") (pintype "passive"))
      (node (ref "R10") (pin "1") (pinfunction "1_1") (pintype "passive"))
      (node (ref "R11") (pin "1") (pinfunction "1_1") (pintype "passive"))
      (node (ref "R12") (pin "1") (pinfunction "1_1") (pintype "passive"))
      (node (ref "R8") (pin "2") (pinfunction "2_2") (pintype "passive"))
      (node (ref "U2") (pin "4") (pinfunction "IN_4") (pintype "passive"))
      (node (ref "U4") (pin "1") (pinfunction "VIN_1") (pintype "passive"))
    )
    (net (code "73") (name "GND") (class "Default")
      (node (ref "C1") (pin "2") (pinfunction "2_2") (pintype "passive"))
      (node (ref "C10") (pin "2") (pinfunction "2_2") (pintype "passive"))
      (node (ref "C2") (pin "2") (pinfunction "2_2") (pintype "passive"))
      (node (ref "C3") (pin "2") (pinfunction "2_2") (pintype "passive"))
      (node (ref "C4") (pin "2") (pinfunction "2_2") (pintype "passive"))
      (node (ref "C5") (pin "2") (pinfunction "2_2") (pintype "passive"))
      (node (ref "C6") (pin "2") (pinfunction "2_2") (pintype "passive"))
      (node (ref "C7") (pin "2") (pinfunction "2_2") (pintype "passive"))
      (node (ref "C8") (pin "2") (pinfunction "2_2") (pintype "passive"))
      (node (ref "C9") (pin "1") (pinfunction "1_1") (pintype "passive"))
      (node (ref "D1") (pin "2") (pinfunction "A_2") (pintype "passive"))
      (node (ref "D10") (pin "1") (pinfunction "A_1") (pintype "passive"))
      (node (ref "D12") (pin "1") (pinfunction "A_1") (pintype "passive"))
      (node (ref "D2") (pin "2") (pinfunction "A_2") (pintype "passive"))
      (node (ref "D3") (pin "2") (pinfunction "A_2") (pintype "passive"))
      (node (ref "D4") (pin "2") (pinfunction "A_2") (pintype "passive"))
      (node (ref "D5") (pin "2") (pinfunction "A_2") (pintype "passive"))
      (node (ref "D6") (pin "2") (pinfunction "A_2") (pintype "passive"))
      (node (ref "D7") (pin "2") (pinfunction "A_2") (pintype "passive"))
      (node (ref "D9") (pin "C") (pinfunction "C_C") (pintype "passive"))
      (node (ref "FM1") (pin "2") (pinfunction "－_2") (pintype "passive"))
      (node (ref "J1") (pin "1") (pinfunction "1_1") (pintype "passive"))
      (node (ref "J12") (pin "2") (pinfunction "2_2") (pintype "passive"))
      (node (ref "J2") (pin "1") (pinfunction "1_1") (pintype "passive"))
      (node (ref "J3") (pin "1") (pinfunction "1_1") (pintype "passive"))
      (node (ref "J4") (pin "1") (pinfunction "1_1") (pintype "passive"))
      (node (ref "J5") (pin "1") (pinfunction "1_1") (pintype "passive"))
      (node (ref "J6") (pin "2") (pinfunction "2_2") (pintype "passive"))
      (node (ref "J7") (pin "1") (pinfunction "1_1") (pintype "passive"))
      (node (ref "J8") (pin "10") (pinfunction "10_10") (pintype "passive"))
      (node (ref "J8") (pin "12") (pinfunction "12_12") (pintype "passive"))
      (node (ref "J9") (pin "1") (pinfunction "1_1") (pintype "passive"))
      (node (ref "JP1") (pin "8") (pinfunction "8_8") (pintype "passive"))
      (node (ref "K1") (pin "A") (pinfunction "A_A") (pintype "passive"))
      (node (ref "K2") (pin "A") (pinfunction "A_A") (pintype "passive"))
      (node (ref "K3") (pin "A") (pinfunction "A_A") (pintype "passive"))
      (node (ref "K4") (pin "A") (pinfunction "A_A") (pintype "passive"))
      (node (ref "K5") (pin "A") (pinfunction "A_A") (pintype "passive"))
      (node (ref "P1") (pin "1") (pinfunction "1_1") (pintype "passive"))
      (node (ref "R14") (pin "2") (pinfunction "2_2") (pintype "passive"))
      (node (ref "R24") (pin "1") (pinfunction "1_1") (pintype "passive"))
      (node (ref "R7") (pin "1") (pinfunction "1_1") (pintype "passive"))
      (node (ref "SW2") (pin "5") (pinfunction "5_5") (pintype "passive"))
      (node (ref "SW2") (pin "6") (pinfunction "6_6") (pintype "passive"))
      (node (ref "SW2") (pin "7") (pinfunction "7_7") (pintype "passive"))
      (node (ref "SW2") (pin "8") (pinfunction "8_8") (pintype "passive"))
      (node (ref "U1") (pin "40") (pinfunction "GND_40") (pintype "passive"))
      (node (ref "U1") (pin "43") (pinfunction "GND_43") (pintype "passive"))
      (node (ref "U2") (pin "7") (pinfunction "GND_7") (pintype "passive"))
      (node (ref "U2") (pin "8") (pinfunction "GND_8") (pintype "passive"))
      (node (ref "U3") (pin "1") (pinfunction "GND_1") (pintype "passive"))
      (node (ref "U4") (pin "3") (pinfunction "GND_3") (pintype "passive"))
      (node (ref "U4") (pin "5") (pinfunction "ON#/OFF_5") (pintype "passive"))
      (node (ref "U4") (pin "6") (pinfunction "GND_6") (pintype "passive"))
      (node (ref "U5") (pin "1") (pinfunction "GND_1") (pintype "passive"))
      (node (ref "U5") (pin "2") (pinfunction "EN_2") (pintype "passive"))
    )
    (net (code "74") (name "Net-(C11-Pad2)") (class "Default")
      (node (ref "C11") (pin "2") (pinfunction "2_2") (pintype "passive"))
      (node (ref "R24") (pin "2") (pinfunction "2_2") (pintype "passive"))
    )
    (net (code "75") (name "Net-(D8-A)") (class "Default")
      (node (ref "D8") (pin "1") (pinfunction "A_1") (pintype "passive"))
      (node (ref "SW1") (pin "2") (pinfunction "C_2") (pintype "passive"))
    )
    (net (code "76") (name "Net-(D8-C)") (class "Default")
      (node (ref "D8") (pin "2") (pinfunction "C_2") (pintype "passive"))
      (node (ref "F1") (pin "1") (pinfunction "1_1") (pintype "passive"))
    )
    (net (code "77") (name "Net-(D9-PadA)") (class "Default")
      (node (ref "D9") (pin "A") (pinfunction "A_A") (pintype "passive"))
      (node (ref "R8") (pin "1") (pinfunction "1_1") (pintype "passive"))
    )
    (net (code "78") (name "Net-(D10-C)") (class "Default")
      (node (ref "D10") (pin "2") (pinfunction "C_2") (pintype "passive"))
      (node (ref "L1") (pin "1") (pinfunction "1_1") (pintype "passive"))
      (node (ref "U2") (pin "5") (pinfunction "SW_5") (pintype "passive"))
      (node (ref "U2") (pin "6") (pinfunction "SW_6") (pintype "passive"))
    )
    (net (code "79") (name "Net-(D11-A)") (class "Default")
      (node (ref "D11") (pin "1") (pinfunction "A_1") (pintype "passive"))
      (node (ref "F3") (pin "2") (pinfunction "2_2") (pintype "passive"))
    )
    (net (code "80") (name "Net-(D12-C)") (class "Default")
      (node (ref "D12") (pin "2") (pinfunction "C_2") (pintype "passive"))
      (node (ref "L2") (pin "2") (pinfunction "2_2") (pintype "passive"))
      (node (ref "U4") (pin "2") (pinfunction "OUTPUT_2") (pintype "passive"))
    )
    (net (code "81") (name "Net-(FM1-+)") (class "Default")
      (node (ref "FM1") (pin "1") (pinfunction "+_1") (pintype "passive"))
      (node (ref "Q1") (pin "3") (pinfunction "C_3") (pintype "passive"))
    )
    (net (code "82") (name "Net-(J1-Pad3)") (class "Default")
      (node (ref "J1") (pin "3") (pinfunction "3_3") (pintype "passive"))
      (node (ref "R2") (pin "2") (pinfunction "2_2") (pintype "passive"))
    )
    (net (code "83") (name "Net-(J3-Pad2)") (class "Default")
      (node (ref "J3") (pin "2") (pinfunction "2_2") (pintype "passive"))
      (node (ref "R4") (pin "2") (pinfunction "2_2") (pintype "passive"))
    )
    (net (code "84") (name "Net-(J5-Pad3)") (class "Default")
      (node (ref "J5") (pin "3") (pinfunction "3_3") (pintype "passive"))
      (node (ref "RN1") (pin "4") (pinfunction "4_4") (pintype "passive"))
    )
    (net (code "85") (name "Net-(J5-Pad4)") (class "Default")
      (node (ref "J5") (pin "4") (pinfunction "4_4") (pintype "passive"))
      (node (ref "RN1") (pin "3") (pinfunction "3_3") (pintype "passive"))
    )
    (net (code "86") (name "Net-(J5-Pad5)") (class "Default")
      (node (ref "J5") (pin "5") (pinfunction "5_5") (pintype "passive"))
      (node (ref "RN1") (pin "2") (pinfunction "2_2") (pintype "passive"))
    )
    (net (code "87") (name "Net-(J5-Pad6)") (class "Default")
      (node (ref "J5") (pin "6") (pinfunction "6_6") (pintype "passive"))
      (node (ref "RN1") (pin "1") (pinfunction "1_1") (pintype "passive"))
    )
    (net (code "88") (name "Net-(J12-Pad3)") (class "Default")
      (node (ref "J12") (pin "3") (pinfunction "3_3") (pintype "passive"))
      (node (ref "R6") (pin "2") (pinfunction "2_2") (pintype "passive"))
    )
    (net (code "89") (name "Net-(J12-Pad4)") (class "Default")
      (node (ref "J12") (pin "4") (pinfunction "4_4") (pintype "passive"))
      (node (ref "R5") (pin "2") (pinfunction "2_2") (pintype "passive"))
    )
    (net (code "90") (name "Net-(Q1-B)") (class "Default")
      (node (ref "Q1") (pin "2") (pinfunction "B_2") (pintype "passive"))
      (node (ref "R15") (pin "2") (pinfunction "2_2") (pintype "passive"))
      (node (ref "R16") (pin "2") (pinfunction "2_2") (pintype "passive"))
    )
    (net (code "91") (name "Net-(R12-Pad2)") (class "Default")
      (node (ref "R12") (pin "2") (pinfunction "2_2") (pintype "passive"))
      (node (ref "R13") (pin "1") (pinfunction "1_1") (pintype "passive"))
      (node (ref "R14") (pin "1") (pinfunction "1_1") (pintype "passive"))
    )
    (net (code "92") (name "Net-(U2-EN)") (class "Default")
      (node (ref "R10") (pin "2") (pinfunction "2_2") (pintype "passive"))
      (node (ref "U2") (pin "2") (pinfunction "EN_2") (pintype "passive"))
    )
    (net (code "93") (name "Net-(U2-FB)") (class "Default")
      (node (ref "R7") (pin "2") (pinfunction "2_2") (pintype "passive"))
      (node (ref "R9") (pin "2") (pinfunction "2_2") (pintype "passive"))
      (node (ref "U2") (pin "1") (pinfunction "FB_1") (pintype "passive"))
    )
    (net (code "94") (name "Net-(U2-OCSET)") (class "Default")
      (node (ref "R11") (pin "2") (pinfunction "2_2") (pintype "passive"))
      (node (ref "U2") (pin "3") (pinfunction "OCSET_3") (pintype "passive"))
    )
    (net (code "95") (name "Net-(U4-FB)") (class "Default")
      (node (ref "C8") (pin "1") (pinfunction "1_1") (pintype "passive"))
      (node (ref "F2") (pin "1") (pinfunction "1_1") (pintype "passive"))
      (node (ref "L2") (pin "1") (pinfunction "1_1") (pintype "passive"))
      (node (ref "U4") (pin "4") (pinfunction "FB_4") (pintype "passive"))
    )
    (net (code "96") (name "Net-(U5-IN)") (class "Default")
      (node (ref "C9") (pin "2") (pinfunction "2_2") (pintype "passive"))
      (node (ref "F3") (pin "1") (pinfunction "1_1") (pintype "passive"))
      (node (ref "U5") (pin "3") (pinfunction "IN/2_3") (pintype "passive"))
      (node (ref "U5") (pin "4") (pinfunction "IN_4") (pintype "passive"))
    )
    (net (code "97") (name "Net-(U5-OUT)") (class "Default")
      (node (ref "C10") (pin "1") (pinfunction "1_1") (pintype "passive"))
      (node (ref "C11") (pin "1") (pinfunction "1_1") (pintype "passive"))
      (node (ref "R22") (pin "1") (pinfunction "1_1") (pintype "passive"))
      (node (ref "R23") (pin "2") (pinfunction "2_2") (pintype "passive"))
      (node (ref "U5") (pin "5") (pinfunction "OUT/2_5") (pintype "passive"))
      (node (ref "U5") (pin "6") (pinfunction "OUT_6") (pintype "passive"))
      (node (ref "U5") (pin "7") (pinfunction "SENSEFB_7") (pintype "passive"))
    )
    (net (code "98") (name "Net-(U5-RESET)") (class "Default")
      (node (ref "R23") (pin "1") (pinfunction "1_1") (pintype "passive"))
      (node (ref "U5") (pin "8") (pinfunction "RESET_8") (pintype "passive"))
    )
    (net (code "99") (name "VCC3.3_MCU") (class "Default")
      (node (ref "R22") (pin "2") (pinfunction "2_2") (pintype "passive"))
      (node (ref "U1") (pin "46") (pinfunction "3V3_46") (pintype "passive"))
      (node (ref "U1") (pin "6") (pinfunction "VREF+_6") (pintype "passive"))
    )
    (net (code "100") (name "VCC_3.3V") (class "Default")
      (node (ref "C5") (pin "1") (pinfunction "1_1") (pintype "passive"))
      (node (ref "J4") (pin "2") (pinfunction "2_2") (pintype "passive"))
      (node (ref "J6") (pin "1") (pinfunction "1_1") (pintype "passive"))
      (node (ref "J8") (pin "11") (pinfunction "11_11") (pintype "passive"))
      (node (ref "Q1") (pin "1") (pinfunction "E_1") (pintype "passive"))
      (node (ref "R15") (pin "1") (pinfunction "1_1") (pintype "passive"))
      (node (ref "R17") (pin "2") (pinfunction "2_2") (pintype "passive"))
      (node (ref "R18") (pin "2") (pinfunction "2_2") (pintype "passive"))
      (node (ref "R19") (pin "2") (pinfunction "2_2") (pintype "passive"))
      (node (ref "R20") (pin "2") (pinfunction "2_2") (pintype "passive"))
      (node (ref "R21") (pin "2") (pinfunction "2_2") (pintype "passive"))
      (node (ref "R4") (pin "1") (pinfunction "1_1") (pintype "passive"))
      (node (ref "RN2") (pin "5") (pinfunction "5_5") (pintype "passive"))
      (node (ref "RN2") (pin "6") (pinfunction "6_6") (pintype "passive"))
      (node (ref "RN2") (pin "7") (pinfunction "7_7") (pintype "passive"))
      (node (ref "RN2") (pin "8") (pinfunction "8_8") (pintype "passive"))
      (node (ref "U3") (pin "2") (pinfunction "Out_2") (pintype "passive"))
      (node (ref "U3") (pin "4") (pinfunction "TAB_4") (pintype "passive"))
    )
    (net (code "101") (name "VCC_5V") (class "Default")
      (node (ref "C4") (pin "1") (pinfunction "1_1") (pintype "passive"))
      (node (ref "D11") (pin "2") (pinfunction "C_2") (pintype "passive"))
      (node (ref "F2") (pin "2") (pinfunction "2_2") (pintype "passive"))
      (node (ref "J12") (pin "1") (pinfunction "1_1") (pintype "passive"))
      (node (ref "J5") (pin "2") (pinfunction "2_2") (pintype "passive"))
      (node (ref "J7") (pin "6") (pinfunction "6_6") (pintype "passive"))
      (node (ref "J9") (pin "6") (pinfunction "6_6") (pintype "passive"))
      (node (ref "U3") (pin "3") (pinfunction "In_3") (pintype "passive"))
    )
    (net (code "102") (name "unconnected-(J2-Pad6)") (class "Default")
      (node (ref "J2") (pin "6") (pinfunction "6_6") (pintype "passive"))
    )
    (net (code "103") (name "unconnected-(J7-Pad3)") (class "Default")
      (node (ref "J7") (pin "3") (pinfunction "3_3") (pintype "passive"))
    )
    (net (code "104") (name "unconnected-(J7-Pad4)") (class "Default")
      (node (ref "J7") (pin "4") (pinfunction "4_4") (pintype "passive"))
    )
    (net (code "105") (name "unconnected-(J8-Pad1)") (class "Default")
      (node (ref "J8") (pin "1") (pinfunction "1_1") (pintype "passive"))
    )
    (net (code "106") (name "unconnected-(J8-Pad2)") (class "Default")
      (node (ref "J8") (pin "2") (pinfunction "2_2") (pintype "passive"))
    )
    (net (code "107") (name "unconnected-(J8-Pad19)") (class "Default")
      (node (ref "J8") (pin "19") (pinfunction "19_19") (pintype "passive"))
    )
    (net (code "108") (name "unconnected-(J8-Pad20)") (class "Default")
      (node (ref "J8") (pin "20") (pinfunction "20_20") (pintype "passive"))
    )
    (net (code "109") (name "unconnected-(J9-Pad3)") (class "Default")
      (node (ref "J9") (pin "3") (pinfunction "3_3") (pintype "passive"))
    )
    (net (code "110") (name "unconnected-(J9-Pad4)") (class "Default")
      (node (ref "J9") (pin "4") (pinfunction "4_4") (pintype "passive"))
    )
    (net (code "111") (name "unconnected-(JP1-Pad3)") (class "Default")
      (node (ref "JP1") (pin "3") (pinfunction "3_3") (pintype "passive"))
    )
    (net (code "112") (name "unconnected-(R7-Pad3)") (class "Default")
      (node (ref "R7") (pin "3") (pinfunction "3_3") (pintype "passive"))
    )
    (net (code "113") (name "unconnected-(SW1-ON-Pad1)") (class "Default")
      (node (ref "SW1") (pin "1") (pinfunction "ON_1") (pintype "passive"))
    )
    (net (code "114") (name "unconnected-(U1A-AN24-Pad125)") (class "Default")
      (node (ref "U1") (pin "125") (pinfunction "AN24_125") (pintype "passive"))
    )
    (net (code "115") (name "unconnected-(U1A-AN36-Pad122)") (class "Default")
      (node (ref "U1") (pin "122") (pinfunction "AN36_122") (pintype "passive"))
    )
    (net (code "116") (name "unconnected-(U1A-AN39-Pad119)") (class "Default")
      (node (ref "U1") (pin "119") (pinfunction "AN39_119") (pintype "passive"))
    )
    (net (code "117") (name "unconnected-(U1A-AN46-Pad116)") (class "Default")
      (node (ref "U1") (pin "116") (pinfunction "AN46_116") (pintype "passive"))
    )
    (net (code "118") (name "unconnected-(U1A-AN49-Pad113)") (class "Default")
      (node (ref "U1") (pin "113") (pinfunction "AN49_113") (pintype "passive"))
    )
    (net (code "119") (name "unconnected-(U1B-AN13-Pad126)") (class "Default")
      (node (ref "U1") (pin "126") (pinfunction "AN13_126") (pintype "passive"))
    )
    (net (code "120") (name "unconnected-(U1B-AN16-Pad124)") (class "Default")
      (node (ref "U1") (pin "124") (pinfunction "AN16_124") (pintype "passive"))
    )
    (net (code "121") (name "unconnected-(U1B-AN17-Pad123)") (class "Default")
      (node (ref "U1") (pin "123") (pinfunction "AN17_123") (pintype "passive"))
    )
    (net (code "122") (name "unconnected-(U1B-AN20-Pad127)") (class "Default")
      (node (ref "U1") (pin "127") (pinfunction "AN20_127") (pintype "passive"))
    )
    (net (code "123") (name "unconnected-(U1B-AN25-Pad120)") (class "Default")
      (node (ref "U1") (pin "120") (pinfunction "AN25_120") (pintype "passive"))
    )
    (net (code "124") (name "unconnected-(U1B-AN35-Pad121)") (class "Default")
      (node (ref "U1") (pin "121") (pinfunction "AN35_121") (pintype "passive"))
    )
    (net (code "125") (name "unconnected-(U1B-AN37-Pad117)") (class "Default")
      (node (ref "U1") (pin "117") (pinfunction "AN37_117") (pintype "passive"))
    )
    (net (code "126") (name "unconnected-(U1B-AN38-Pad118)") (class "Default")
      (node (ref "U1") (pin "118") (pinfunction "AN38_118") (pintype "passive"))
    )
    (net (code "127") (name "unconnected-(U1B-AN44-Pad114)") (class "Default")
      (node (ref "U1") (pin "114") (pinfunction "AN44_114") (pintype "passive"))
    )
    (net (code "128") (name "unconnected-(U1B-AN45-Pad115)") (class "Default")
      (node (ref "U1") (pin "115") (pinfunction "AN45_115") (pintype "passive"))
    )
    (net (code "129") (name "unconnected-(U1B-AN47-Pad111)") (class "Default")
      (node (ref "U1") (pin "111") (pinfunction "AN47_111") (pintype "passive"))
    )
    (net (code "130") (name "unconnected-(U1B-AN48-Pad112)") (class "Default")
      (node (ref "U1") (pin "112") (pinfunction "AN48_112") (pintype "passive"))
    )
    (net (code "131") (name "unconnected-(U1B-P00.12-Pad108)") (class "Default")
      (node (ref "U1") (pin "108") (pinfunction "P00.12_108") (pintype "passive"))
    )
    (net (code "132") (name "unconnected-(U1B-P10.6{slash}#5-Pad90)") (class "Default")
      (node (ref "U1") (pin "90") (pinfunction "P10.6/#5_90") (pintype "passive"))
    )
    (net (code "133") (name "unconnected-(U1C-P10.5{slash}#4-Pad87)") (class "Default")
      (node (ref "U1") (pin "87") (pinfunction "P10.5/#4_87") (pintype "passive"))
    )
    (net (code "134") (name "unconnected-(U1C-P13.0-Pad74)") (class "Default")
      (node (ref "U1") (pin "74") (pinfunction "P13.0_74") (pintype "passive"))
    )
    (net (code "135") (name "unconnected-(U1C-P13.3-Pad78)") (class "Default")
      (node (ref "U1") (pin "78") (pinfunction "P13.3_78") (pintype "passive"))
    )
    (net (code "136") (name "unconnected-(U1C-P14.2{slash}#2-Pad71)") (class "Default")
      (node (ref "U1") (pin "71") (pinfunction "P14.2/#2_71") (pintype "passive"))
    )
    (net (code "137") (name "unconnected-(U1C-P14.3{slash}#3-Pad73)") (class "Default")
      (node (ref "U1") (pin "73") (pinfunction "P14.3/#3_73") (pintype "passive"))
    )
    (net (code "138") (name "unconnected-(U1C-P14.4{slash}#6-Pad70)") (class "Default")
      (node (ref "U1") (pin "70") (pinfunction "P14.4/#6_70") (pintype "passive"))
    )
    (net (code "139") (name "unconnected-(U1C-P14.5{slash}#1-Pad72)") (class "Default")
      (node (ref "U1") (pin "72") (pinfunction "P14.5/#1_72") (pintype "passive"))
    )
    (net (code "140") (name "unconnected-(U1C-P14.6{slash}#0-Pad75)") (class "Default")
      (node (ref "U1") (pin "75") (pinfunction "P14.6/#0_75") (pintype "passive"))
    )
    (net (code "141") (name "unconnected-(U1C-P15.0-Pad65)") (class "Default")
      (node (ref "U1") (pin "65") (pinfunction "P15.0_65") (pintype "passive"))
    )
    (net (code "142") (name "unconnected-(U1C-P15.2-Pad67)") (class "Default")
      (node (ref "U1") (pin "67") (pinfunction "P15.2_67") (pintype "passive"))
    )
    (net (code "143") (name "unconnected-(U1C-P15.3-Pad66)") (class "Default")
      (node (ref "U1") (pin "66") (pinfunction "P15.3_66") (pintype "passive"))
    )
    (net (code "144") (name "unconnected-(U1C-P15.7-Pad69)") (class "Default")
      (node (ref "U1") (pin "69") (pinfunction "P15.7_69") (pintype "passive"))
    )
    (net (code "145") (name "unconnected-(U1C-P15.8-Pad68)") (class "Default")
      (node (ref "U1") (pin "68") (pinfunction "P15.8_68") (pintype "passive"))
    )
    (net (code "146") (name "unconnected-(U1D-AN2-Pad11)") (class "Default")
      (node (ref "U1") (pin "11") (pinfunction "AN2_11") (pintype "passive"))
    )
    (net (code "147") (name "unconnected-(U1D-AN8-Pad8)") (class "Default")
      (node (ref "U1") (pin "8") (pinfunction "AN8_8") (pintype "passive"))
    )
    (net (code "148") (name "unconnected-(U1D-AN10-Pad3)") (class "Default")
      (node (ref "U1") (pin "3") (pinfunction "AN10_3") (pintype "passive"))
    )
    (net (code "149") (name "unconnected-(U1D-AN11-Pad4)") (class "Default")
      (node (ref "U1") (pin "4") (pinfunction "AN11_4") (pintype "passive"))
    )
    (net (code "150") (name "unconnected-(U1D-AN12-Pad1)") (class "Default")
      (node (ref "U1") (pin "1") (pinfunction "AN12_1") (pintype "passive"))
    )
    (net (code "151") (name "unconnected-(U1D-P33.4-Pad15)") (class "Default")
      (node (ref "U1") (pin "15") (pinfunction "P33.4_15") (pintype "passive"))
    )
    (net (code "152") (name "unconnected-(U1D-P33.5-Pad16)") (class "Default")
      (node (ref "U1") (pin "16") (pinfunction "P33.5_16") (pintype "passive"))
    )
    (net (code "153") (name "unconnected-(U1D-P33.8-Pad18)") (class "Default")
      (node (ref "U1") (pin "18") (pinfunction "P33.8_18") (pintype "passive"))
    )
    (net (code "154") (name "unconnected-(U1D-P33.10-Pad21)") (class "Default")
      (node (ref "U1") (pin "21") (pinfunction "P33.10_21") (pintype "passive"))
    )
    (net (code "155") (name "unconnected-(U1E-ESR0-Pad51)") (class "Default")
      (node (ref "U1") (pin "51") (pinfunction "ESR0_51") (pintype "passive"))
    )
    (net (code "156") (name "unconnected-(U1E-P14.0{slash}TX-Pad37)") (class "Default")
      (node (ref "U1") (pin "37") (pinfunction "P14.0/TX_37") (pintype "passive"))
    )
    (net (code "157") (name "unconnected-(U1E-P14.1{slash}RX-Pad34)") (class "Default")
      (node (ref "U1") (pin "34") (pinfunction "P14.1/RX_34") (pintype "passive"))
    )
    (net (code "158") (name "unconnected-(U1E-P20.6-Pad52)") (class "Default")
      (node (ref "U1") (pin "52") (pinfunction "P20.6_52") (pintype "passive"))
    )
    (net (code "159") (name "unconnected-(U1E-P20.9-Pad55)") (class "Default")
      (node (ref "U1") (pin "55") (pinfunction "P20.9_55") (pintype "passive"))
    )
    (net (code "160") (name "unconnected-(U1E-P32.0{slash}VG1N-Pad26)") (class "Default")
      (node (ref "U1") (pin "26") (pinfunction "P32.0/VG1N_26") (pintype "passive"))
    )
    (net (code "161") (name "unconnected-(U1E-PORST-Pad33)") (class "Default")
      (node (ref "U1") (pin "33") (pinfunction "PORST_33") (pintype "passive"))
    )
    (net (code "162") (name "unconnected-(U1E-TCK-Pad42)") (class "Default")
      (node (ref "U1") (pin "42") (pinfunction "TCK_42") (pintype "passive"))
    )
    (net (code "163") (name "unconnected-(U1E-TDO{slash}P21.7-Pad39)") (class "Default")
      (node (ref "U1") (pin "39") (pinfunction "TDO/P21.7_39") (pintype "passive"))
    )
    (net (code "164") (name "unconnected-(U1E-TMS-Pad45)") (class "Default")
      (node (ref "U1") (pin "45") (pinfunction "TMS_45") (pintype "passive"))
    )
    (net (code "165") (name "unconnected-(U1E-TRST-Pad36)") (class "Default")
      (node (ref "U1") (pin "36") (pinfunction "TRST_36") (pintype "passive"))
    )
    (net (code "166") (name "unconnected-(U1E-VGATE1P-Pad25)") (class "Default")
      (node (ref "U1") (pin "25") (pinfunction "VGATE1P_25") (pintype "passive"))
    )
    (net (code "167") (name "unconnected-(U1F-ESR1-Pad50)") (class "Default")
      (node (ref "U1") (pin "50") (pinfunction "ESR1_50") (pintype "passive"))
    )
    (net (code "168") (name "unconnected-(U1F-P20.7-Pad53)") (class "Default")
      (node (ref "U1") (pin "53") (pinfunction "P20.7_53") (pintype "passive"))
    )
    (net (code "169") (name "unconnected-(U1F-P21.3-Pad38)") (class "Default")
      (node (ref "U1") (pin "38") (pinfunction "P21.3_38") (pintype "passive"))
    )
    (net (code "170") (name "unconnected-(U1F-P21.4-Pad41)") (class "Default")
      (node (ref "U1") (pin "41") (pinfunction "P21.4_41") (pintype "passive"))
    )
    (net (code "171") (name "unconnected-(U1F-P21.5-Pad44)") (class "Default")
      (node (ref "U1") (pin "44") (pinfunction "P21.5_44") (pintype "passive"))
    )
    (net (code "172") (name "unconnected-(U1F-P21.~{6}TDI-Pad47)") (class "Default")
      (node (ref "U1") (pin "47") (pinfunction "P21.~{6}TDI_47") (pintype "passive"))
    )
  )
)
